# rapidshark-display-shifter-mk-3_1.net
KiCad netlist of a schematic drawn in EAGLE
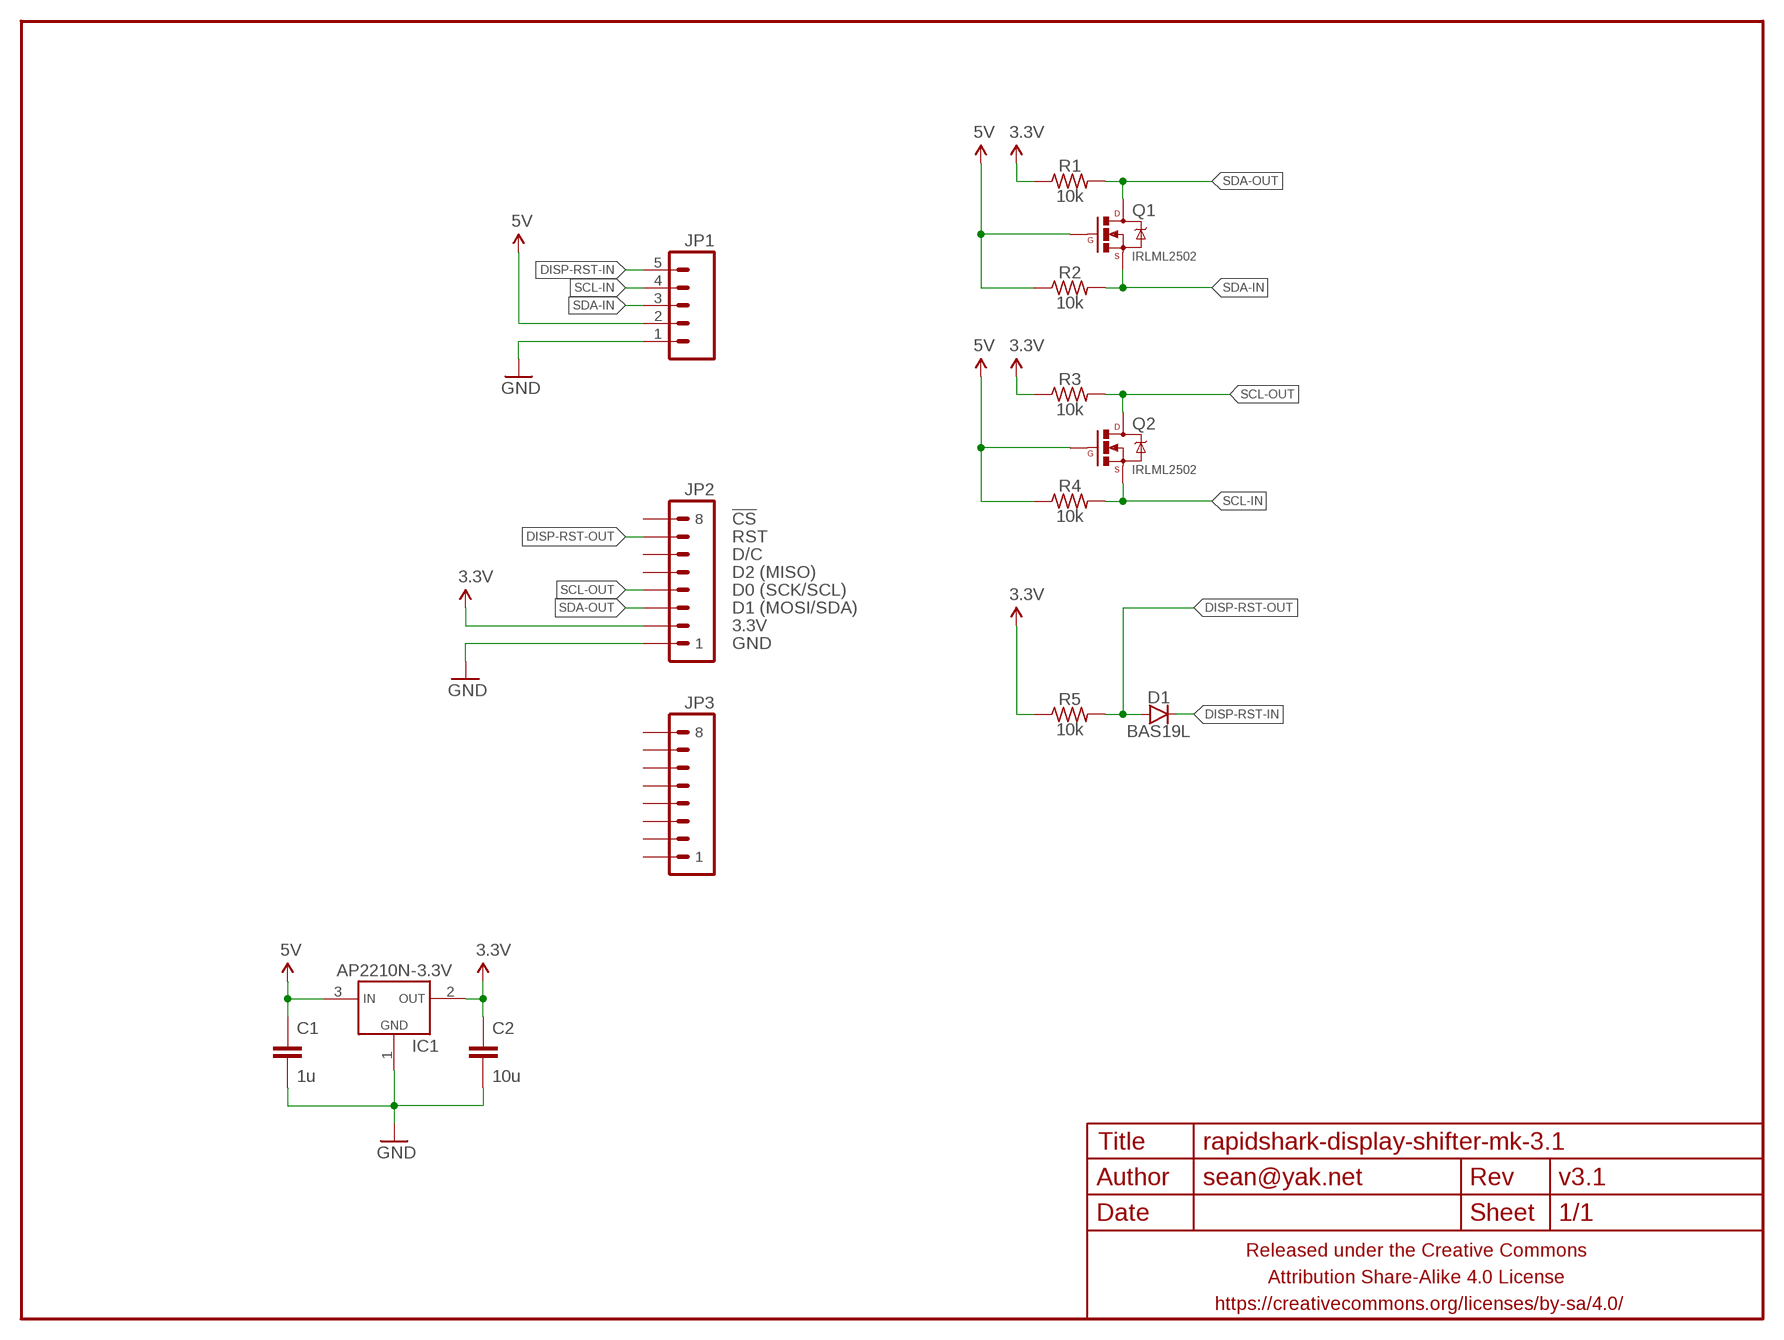
[diagram p0: schematic, sheet 1]

(export (version "E")
  (design (tool "Eeschema 10.0.6"))
  (components
    (comp (ref "C1")
      (value "1u")
      (footprint "eagle-import:C0805")
      (libsource (lib "eagle-import") (part "CAPACITOR-CERAMICC0805"))
    )
    (comp (ref "C2")
      (value "10u")
      (footprint "eagle-import:C0805")
      (libsource (lib "eagle-import") (part "CAPACITOR-CERAMICC0805"))
    )
    (comp (ref "D1")
      (value "BAS19L")
      (footprint "eagle-import:SOT23")
      (libsource (lib "eagle-import") (part "DIODESOT23"))
    )
    (comp (ref "FRAME1")
      (value "FRAME-LETTERNO_PACKAGE")
      (footprint "eagle-import:DUMMY")
      (fields (field (name "DESIGNER") "sean@yak.net") (field (name "VERSION") "v3.1"))
      (libsource (lib "eagle-import") (part "FRAME-LETTERNO_PACKAGE"))
    )
    (comp (ref "IC1")
      (value "AP2210N-3.3V")
      (footprint "eagle-import:SOT23")
      (libsource (lib "eagle-import") (part "VREG_1117SOT-23"))
    )
    (comp (ref "JP1")
      (value "M05PTH-CENTERED")
      (footprint "eagle-import:1X05_PTH_CENTERED")
      (libsource (lib "eagle-import") (part "M05PTH-CENTERED"))
    )
    (comp (ref "JP2")
      (value "M081X08")
      (footprint "eagle-import:1X08")
      (libsource (lib "eagle-import") (part "M081X08"))
    )
    (comp (ref "JP3")
      (value "M081X08")
      (footprint "eagle-import:1X08")
      (libsource (lib "eagle-import") (part "M081X08"))
    )
    (comp (ref "Q1")
      (value "IRLML2502")
      (footprint "eagle-import:SOT23")
      (libsource (lib "eagle-import") (part "MOSFET-NCHANNELIRLML2502"))
    )
    (comp (ref "Q2")
      (value "IRLML2502")
      (footprint "eagle-import:SOT23")
      (libsource (lib "eagle-import") (part "MOSFET-NCHANNELIRLML2502"))
    )
    (comp (ref "R1")
      (value "10k")
      (footprint "eagle-import:R0603")
      (libsource (lib "eagle-import") (part "RESISTORR0603"))
    )
    (comp (ref "R2")
      (value "10k")
      (footprint "eagle-import:R0603")
      (libsource (lib "eagle-import") (part "RESISTORR0603"))
    )
    (comp (ref "R3")
      (value "10k")
      (footprint "eagle-import:R0603")
      (libsource (lib "eagle-import") (part "RESISTORR0603"))
    )
    (comp (ref "R4")
      (value "10k")
      (footprint "eagle-import:R0603")
      (libsource (lib "eagle-import") (part "RESISTORR0603"))
    )
    (comp (ref "R5")
      (value "10k")
      (footprint "eagle-import:R0603")
      (libsource (lib "eagle-import") (part "RESISTORR0603"))
    )
  )
  (nets
    (net (code "1") (name "3.3V") (class "Default")
      (node (ref "C2") (pin "1") (pinfunction "1_1") (pintype "passive"))
      (node (ref "IC1") (pin "2") (pinfunction "VOUT_2") (pintype "bidirectional"))
      (node (ref "JP2") (pin "2") (pinfunction "2_2") (pintype "passive"))
      (node (ref "R1") (pin "1") (pinfunction "1_1") (pintype "passive"))
      (node (ref "R3") (pin "1") (pinfunction "1_1") (pintype "passive"))
      (node (ref "R5") (pin "1") (pinfunction "1_1") (pintype "passive"))
    )
    (net (code "2") (name "5V") (class "Default")
      (node (ref "C1") (pin "1") (pinfunction "1_1") (pintype "passive"))
      (node (ref "IC1") (pin "3") (pinfunction "VIN_3") (pintype "bidirectional"))
      (node (ref "JP1") (pin "2") (pinfunction "2_2") (pintype "passive"))
      (node (ref "Q1") (pin "1") (pinfunction "G_1") (pintype "passive"))
      (node (ref "Q2") (pin "1") (pinfunction "G_1") (pintype "passive"))
      (node (ref "R2") (pin "1") (pinfunction "1_1") (pintype "passive"))
      (node (ref "R4") (pin "1") (pinfunction "1_1") (pintype "passive"))
    )
    (net (code "3") (name "DISP-RST-IN") (class "Default")
      (node (ref "D1") (pin "3") (pinfunction "C_3") (pintype "passive"))
      (node (ref "JP1") (pin "5") (pinfunction "5_5") (pintype "passive"))
    )
    (net (code "4") (name "DISP-RST-OUT") (class "Default")
      (node (ref "D1") (pin "1") (pinfunction "A_1") (pintype "passive"))
      (node (ref "JP2") (pin "7") (pinfunction "7_7") (pintype "passive"))
      (node (ref "R5") (pin "2") (pinfunction "2_2") (pintype "passive"))
    )
    (net (code "5") (name "GND") (class "Default")
      (node (ref "C1") (pin "2") (pinfunction "2_2") (pintype "passive"))
      (node (ref "C2") (pin "2") (pinfunction "2_2") (pintype "passive"))
      (node (ref "IC1") (pin "1") (pinfunction "GND_1") (pintype "bidirectional"))
      (node (ref "JP1") (pin "1") (pinfunction "1_1") (pintype "passive"))
      (node (ref "JP2") (pin "1") (pinfunction "1_1") (pintype "passive"))
    )
    (net (code "6") (name "SCL-IN") (class "Default")
      (node (ref "JP1") (pin "4") (pinfunction "4_4") (pintype "passive"))
      (node (ref "Q2") (pin "2") (pinfunction "S_2") (pintype "passive"))
      (node (ref "R4") (pin "2") (pinfunction "2_2") (pintype "passive"))
    )
    (net (code "7") (name "SCL-OUT") (class "Default")
      (node (ref "JP2") (pin "4") (pinfunction "4_4") (pintype "passive"))
      (node (ref "Q2") (pin "3") (pinfunction "D_3") (pintype "passive"))
      (node (ref "R3") (pin "2") (pinfunction "2_2") (pintype "passive"))
    )
    (net (code "8") (name "SDA-IN") (class "Default")
      (node (ref "JP1") (pin "3") (pinfunction "3_3") (pintype "passive"))
      (node (ref "Q1") (pin "2") (pinfunction "S_2") (pintype "passive"))
      (node (ref "R2") (pin "2") (pinfunction "2_2") (pintype "passive"))
    )
    (net (code "9") (name "SDA-OUT") (class "Default")
      (node (ref "JP2") (pin "3") (pinfunction "3_3") (pintype "passive"))
      (node (ref "Q1") (pin "3") (pinfunction "D_3") (pintype "passive"))
      (node (ref "R1") (pin "2") (pinfunction "2_2") (pintype "passive"))
    )
    (net (code "10") (name "unconnected-(JP2-Pad5)") (class "Default")
      (node (ref "JP2") (pin "5") (pinfunction "5_5") (pintype "passive"))
    )
    (net (code "11") (name "unconnected-(JP2-Pad6)") (class "Default")
      (node (ref "JP2") (pin "6") (pinfunction "6_6") (pintype "passive"))
    )
    (net (code "12") (name "unconnected-(JP2-Pad8)") (class "Default")
      (node (ref "JP2") (pin "8") (pinfunction "8_8") (pintype "passive"))
    )
    (net (code "13") (name "unconnected-(JP3-Pad1)") (class "Default")
      (node (ref "JP3") (pin "1") (pinfunction "1_1") (pintype "passive"))
    )
    (net (code "14") (name "unconnected-(JP3-Pad2)") (class "Default")
      (node (ref "JP3") (pin "2") (pinfunction "2_2") (pintype "passive"))
    )
    (net (code "15") (name "unconnected-(JP3-Pad3)") (class "Default")
      (node (ref "JP3") (pin "3") (pinfunction "3_3") (pintype "passive"))
    )
    (net (code "16") (name "unconnected-(JP3-Pad4)") (class "Default")
      (node (ref "JP3") (pin "4") (pinfunction "4_4") (pintype "passive"))
    )
    (net (code "17") (name "unconnected-(JP3-Pad5)") (class "Default")
      (node (ref "JP3") (pin "5") (pinfunction "5_5") (pintype "passive"))
    )
    (net (code "18") (name "unconnected-(JP3-Pad6)") (class "Default")
      (node (ref "JP3") (pin "6") (pinfunction "6_6") (pintype "passive"))
    )
    (net (code "19") (name "unconnected-(JP3-Pad7)") (class "Default")
      (node (ref "JP3") (pin "7") (pinfunction "7_7") (pintype "passive"))
    )
    (net (code "20") (name "unconnected-(JP3-Pad8)") (class "Default")
      (node (ref "JP3") (pin "8") (pinfunction "8_8") (pintype "passive"))
    )
  )
)
